# board_3.net
KiCad netlist of a schematic drawn in EAGLE
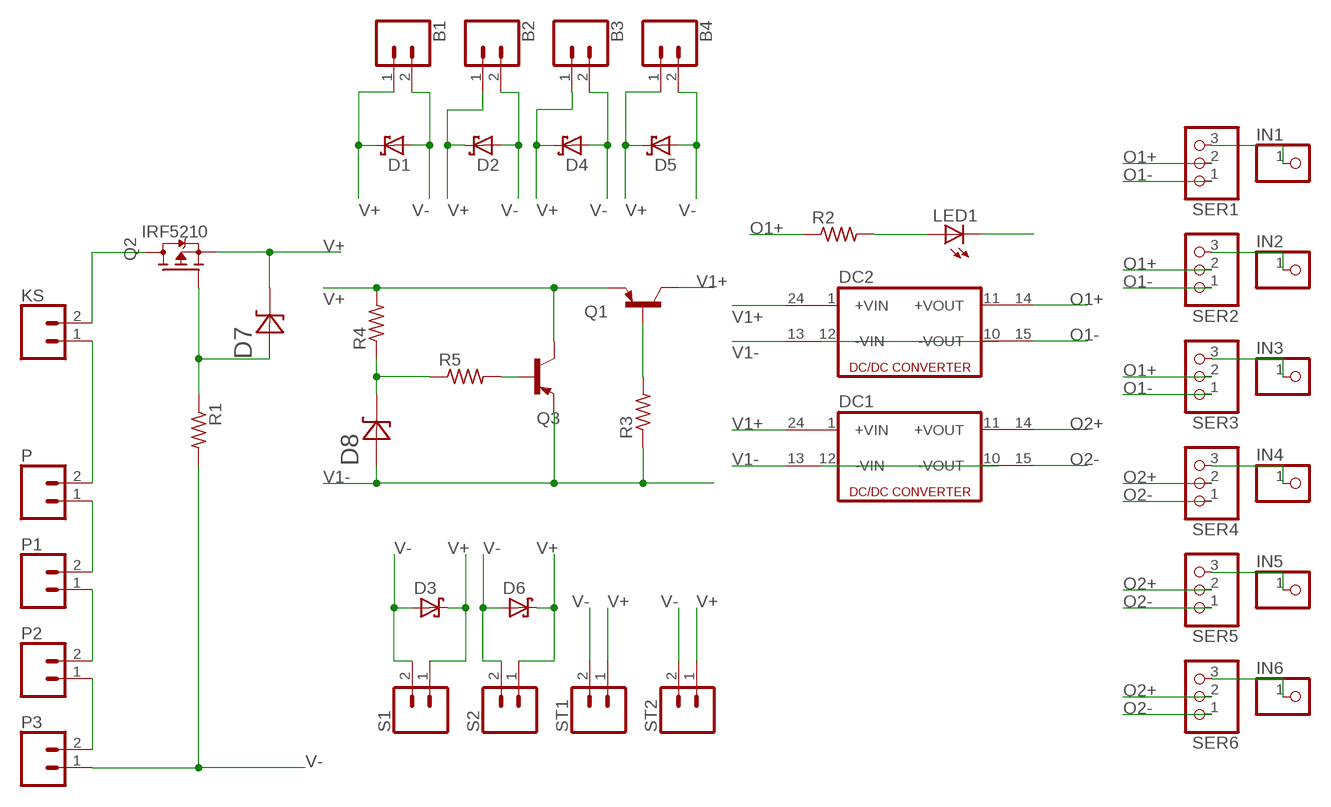
[diagram p0: schematic, sheet 1]

(export (version "E")
  (design (tool "Eeschema 10.0.6"))
  (components
    (comp (ref "B1")
      (value "CONN_02")
      (footprint "eagle-import:1X02")
      (libsource (lib "eagle-import") (part "CONN_02"))
    )
    (comp (ref "B2")
      (value "CONN_02")
      (footprint "eagle-import:1X02")
      (libsource (lib "eagle-import") (part "CONN_02"))
    )
    (comp (ref "B3")
      (value "CONN_02")
      (footprint "eagle-import:1X02")
      (libsource (lib "eagle-import") (part "CONN_02"))
    )
    (comp (ref "B4")
      (value "CONN_02")
      (footprint "eagle-import:1X02")
      (libsource (lib "eagle-import") (part "CONN_02"))
    )
    (comp (ref "D1")
      (value "SCHOTTKY-DIODEF126Z12")
      (footprint "eagle-import:F126Z12")
      (libsource (lib "eagle-import") (part "SCHOTTKY-DIODEF126Z12"))
    )
    (comp (ref "D2")
      (value "SCHOTTKY-DIODEF126Z12")
      (footprint "eagle-import:F126Z12")
      (libsource (lib "eagle-import") (part "SCHOTTKY-DIODEF126Z12"))
    )
    (comp (ref "D3")
      (value "SCHOTTKY-DIODEF126Z12")
      (footprint "eagle-import:F126Z12")
      (libsource (lib "eagle-import") (part "SCHOTTKY-DIODEF126Z12"))
    )
    (comp (ref "D4")
      (value "SCHOTTKY-DIODEF126Z12")
      (footprint "eagle-import:F126Z12")
      (libsource (lib "eagle-import") (part "SCHOTTKY-DIODEF126Z12"))
    )
    (comp (ref "D5")
      (value "SCHOTTKY-DIODEF126Z12")
      (footprint "eagle-import:F126Z12")
      (libsource (lib "eagle-import") (part "SCHOTTKY-DIODEF126Z12"))
    )
    (comp (ref "D6")
      (value "SCHOTTKY-DIODEF126Z12")
      (footprint "eagle-import:F126Z12")
      (libsource (lib "eagle-import") (part "SCHOTTKY-DIODEF126Z12"))
    )
    (comp (ref "D7")
      (value "1N4752A-T")
      (footprint "eagle-import:DIOAD1060W80L410D260")
      (fields (field (name "MF") "ON Semiconductor") (field (name "MP") "1N4752A"))
      (libsource (lib "eagle-import") (part "1N4752A-T"))
    )
    (comp (ref "D8")
      (value "1N4752A-T")
      (footprint "eagle-import:DIOAD1060W80L410D260")
      (fields (field (name "MF") "ON Semiconductor") (field (name "MP") "1N4752A"))
      (libsource (lib "eagle-import") (part "1N4752A-T"))
    )
    (comp (ref "DC1")
      (value "DC213R")
      (footprint "eagle-import:CMK")
      (libsource (lib "eagle-import") (part "DC213R"))
    )
    (comp (ref "DC2")
      (value "DC213R")
      (footprint "eagle-import:CMK")
      (libsource (lib "eagle-import") (part "DC213R"))
    )
    (comp (ref "IN1")
      (value "PINHD-1X1")
      (footprint "eagle-import:1X01")
      (libsource (lib "eagle-import") (part "PINHD-1X1"))
    )
    (comp (ref "IN2")
      (value "PINHD-1X1")
      (footprint "eagle-import:1X01")
      (libsource (lib "eagle-import") (part "PINHD-1X1"))
    )
    (comp (ref "IN3")
      (value "PINHD-1X1")
      (footprint "eagle-import:1X01")
      (libsource (lib "eagle-import") (part "PINHD-1X1"))
    )
    (comp (ref "IN4")
      (value "PINHD-1X1")
      (footprint "eagle-import:1X01")
      (libsource (lib "eagle-import") (part "PINHD-1X1"))
    )
    (comp (ref "IN5")
      (value "PINHD-1X1")
      (footprint "eagle-import:1X01")
      (libsource (lib "eagle-import") (part "PINHD-1X1"))
    )
    (comp (ref "IN6")
      (value "PINHD-1X1")
      (footprint "eagle-import:1X01")
      (libsource (lib "eagle-import") (part "PINHD-1X1"))
    )
    (comp (ref "KS")
      (value "CONN_02")
      (footprint "eagle-import:1X02")
      (libsource (lib "eagle-import") (part "CONN_02"))
    )
    (comp (ref "LED1")
      (value "LED5MM")
      (footprint "eagle-import:LED5MM")
      (libsource (lib "eagle-import") (part "LED5MM"))
    )
    (comp (ref "P")
      (value "CONN_02")
      (footprint "eagle-import:1X02")
      (libsource (lib "eagle-import") (part "CONN_02"))
    )
    (comp (ref "P1")
      (value "CONN_02")
      (footprint "eagle-import:1X02")
      (libsource (lib "eagle-import") (part "CONN_02"))
    )
    (comp (ref "P2")
      (value "CONN_02")
      (footprint "eagle-import:1X02")
      (libsource (lib "eagle-import") (part "CONN_02"))
    )
    (comp (ref "P3")
      (value "CONN_02")
      (footprint "eagle-import:1X02")
      (libsource (lib "eagle-import") (part "CONN_02"))
    )
    (comp (ref "Q1")
      (value "2N2907")
      (footprint "eagle-import:TO92-EBC-OVAL")
      (libsource (lib "eagle-import") (part "2N2907"))
    )
    (comp (ref "Q2")
      (value "IRF5210")
      (footprint "eagle-import:TO254P1054X469X2933-3")
      (fields (field (name "MF") "Infineon Technologies"))
      (libsource (lib "eagle-import") (part "IRF5210"))
    )
    (comp (ref "Q3")
      (value "2N2907")
      (footprint "eagle-import:TO92-EBC-OVAL")
      (libsource (lib "eagle-import") (part "2N2907"))
    )
    (comp (ref "R1")
      (value "R-US_0204/7")
      (footprint "eagle-import:0204_7")
      (libsource (lib "eagle-import") (part "R-US_0204/7"))
    )
    (comp (ref "R2")
      (value "R-US_0204/7")
      (footprint "eagle-import:0204_7")
      (libsource (lib "eagle-import") (part "R-US_0204/7"))
    )
    (comp (ref "R3")
      (value "R-US_0204/7")
      (footprint "eagle-import:0204_7")
      (libsource (lib "eagle-import") (part "R-US_0204/7"))
    )
    (comp (ref "R4")
      (value "R-US_0204/7")
      (footprint "eagle-import:0204_7")
      (libsource (lib "eagle-import") (part "R-US_0204/7"))
    )
    (comp (ref "R5")
      (value "R-US_0204/7")
      (footprint "eagle-import:0204_7")
      (libsource (lib "eagle-import") (part "R-US_0204/7"))
    )
    (comp (ref "S1")
      (value "CONN_02")
      (footprint "eagle-import:1X02")
      (libsource (lib "eagle-import") (part "CONN_02"))
    )
    (comp (ref "S2")
      (value "CONN_02")
      (footprint "eagle-import:1X02")
      (libsource (lib "eagle-import") (part "CONN_02"))
    )
    (comp (ref "SER1")
      (value "PINHD-1X3")
      (footprint "eagle-import:1X03")
      (libsource (lib "eagle-import") (part "PINHD-1X3"))
    )
    (comp (ref "SER2")
      (value "PINHD-1X3")
      (footprint "eagle-import:1X03")
      (libsource (lib "eagle-import") (part "PINHD-1X3"))
    )
    (comp (ref "SER3")
      (value "PINHD-1X3")
      (footprint "eagle-import:1X03")
      (libsource (lib "eagle-import") (part "PINHD-1X3"))
    )
    (comp (ref "SER4")
      (value "PINHD-1X3")
      (footprint "eagle-import:1X03")
      (libsource (lib "eagle-import") (part "PINHD-1X3"))
    )
    (comp (ref "SER5")
      (value "PINHD-1X3")
      (footprint "eagle-import:1X03")
      (libsource (lib "eagle-import") (part "PINHD-1X3"))
    )
    (comp (ref "SER6")
      (value "PINHD-1X3")
      (footprint "eagle-import:1X03")
      (libsource (lib "eagle-import") (part "PINHD-1X3"))
    )
    (comp (ref "ST1")
      (value "CONN_02")
      (footprint "eagle-import:1X02")
      (libsource (lib "eagle-import") (part "CONN_02"))
    )
    (comp (ref "ST2")
      (value "CONN_02")
      (footprint "eagle-import:1X02")
      (libsource (lib "eagle-import") (part "CONN_02"))
    )
  )
  (nets
    (net (code "1") (name "/O1+") (class "Default")
      (node (ref "DC2") (pin "14") (pinfunction "+VOUT1_14") (pintype "passive"))
      (node (ref "R2") (pin "1") (pinfunction "1_1") (pintype "passive"))
      (node (ref "SER1") (pin "2") (pinfunction "2_2") (pintype "passive"))
      (node (ref "SER2") (pin "2") (pinfunction "2_2") (pintype "passive"))
      (node (ref "SER3") (pin "2") (pinfunction "2_2") (pintype "passive"))
    )
    (net (code "2") (name "/O1-") (class "Default")
      (node (ref "DC2") (pin "15") (pinfunction "-VOUT1_15") (pintype "passive"))
      (node (ref "SER1") (pin "1") (pinfunction "1_1") (pintype "passive"))
      (node (ref "SER2") (pin "1") (pinfunction "1_1") (pintype "passive"))
      (node (ref "SER3") (pin "1") (pinfunction "1_1") (pintype "passive"))
    )
    (net (code "3") (name "/O2+") (class "Default")
      (node (ref "DC1") (pin "14") (pinfunction "+VOUT1_14") (pintype "passive"))
      (node (ref "SER4") (pin "2") (pinfunction "2_2") (pintype "passive"))
      (node (ref "SER5") (pin "2") (pinfunction "2_2") (pintype "passive"))
      (node (ref "SER6") (pin "2") (pinfunction "2_2") (pintype "passive"))
    )
    (net (code "4") (name "/O2-") (class "Default")
      (node (ref "DC1") (pin "15") (pinfunction "-VOUT1_15") (pintype "passive"))
      (node (ref "SER4") (pin "1") (pinfunction "1_1") (pintype "passive"))
      (node (ref "SER5") (pin "1") (pinfunction "1_1") (pintype "passive"))
      (node (ref "SER6") (pin "1") (pinfunction "1_1") (pintype "passive"))
    )
    (net (code "5") (name "/V+") (class "Default")
      (node (ref "B1") (pin "1") (pinfunction "1_1") (pintype "passive"))
      (node (ref "B2") (pin "1") (pinfunction "1_1") (pintype "passive"))
      (node (ref "B3") (pin "1") (pinfunction "1_1") (pintype "passive"))
      (node (ref "B4") (pin "1") (pinfunction "1_1") (pintype "passive"))
      (node (ref "D1") (pin "C") (pinfunction "C_C") (pintype "passive"))
      (node (ref "D2") (pin "C") (pinfunction "C_C") (pintype "passive"))
      (node (ref "D3") (pin "C") (pinfunction "C_C") (pintype "passive"))
      (node (ref "D4") (pin "C") (pinfunction "C_C") (pintype "passive"))
      (node (ref "D5") (pin "C") (pinfunction "C_C") (pintype "passive"))
      (node (ref "D6") (pin "C") (pinfunction "C_C") (pintype "passive"))
      (node (ref "D7") (pin "C") (pinfunction "C_C") (pintype "passive"))
      (node (ref "Q1") (pin "E") (pinfunction "E_E") (pintype "passive"))
      (node (ref "Q2") (pin "3") (pinfunction "S_3") (pintype "passive"))
      (node (ref "Q3") (pin "C") (pinfunction "C_C") (pintype "passive"))
      (node (ref "R4") (pin "2") (pinfunction "2_2") (pintype "passive"))
      (node (ref "S1") (pin "1") (pinfunction "1_1") (pintype "passive"))
      (node (ref "S2") (pin "1") (pinfunction "1_1") (pintype "passive"))
      (node (ref "ST1") (pin "1") (pinfunction "1_1") (pintype "passive"))
      (node (ref "ST2") (pin "1") (pinfunction "1_1") (pintype "passive"))
    )
    (net (code "6") (name "/V-") (class "Default")
      (node (ref "B1") (pin "2") (pinfunction "2_2") (pintype "passive"))
      (node (ref "B2") (pin "2") (pinfunction "2_2") (pintype "passive"))
      (node (ref "B3") (pin "2") (pinfunction "2_2") (pintype "passive"))
      (node (ref "B4") (pin "2") (pinfunction "2_2") (pintype "passive"))
      (node (ref "D1") (pin "A") (pinfunction "A_A") (pintype "passive"))
      (node (ref "D2") (pin "A") (pinfunction "A_A") (pintype "passive"))
      (node (ref "D3") (pin "A") (pinfunction "A_A") (pintype "passive"))
      (node (ref "D4") (pin "A") (pinfunction "A_A") (pintype "passive"))
      (node (ref "D5") (pin "A") (pinfunction "A_A") (pintype "passive"))
      (node (ref "D6") (pin "A") (pinfunction "A_A") (pintype "passive"))
      (node (ref "P3") (pin "1") (pinfunction "1_1") (pintype "passive"))
      (node (ref "R1") (pin "2") (pinfunction "2_2") (pintype "passive"))
      (node (ref "S1") (pin "2") (pinfunction "2_2") (pintype "passive"))
      (node (ref "S2") (pin "2") (pinfunction "2_2") (pintype "passive"))
      (node (ref "ST1") (pin "2") (pinfunction "2_2") (pintype "passive"))
      (node (ref "ST2") (pin "2") (pinfunction "2_2") (pintype "passive"))
    )
    (net (code "7") (name "/V1+") (class "Default")
      (node (ref "DC1") (pin "24") (pinfunction "+VIN1_24") (pintype "passive"))
      (node (ref "DC2") (pin "24") (pinfunction "+VIN1_24") (pintype "passive"))
      (node (ref "Q1") (pin "C") (pinfunction "C_C") (pintype "passive"))
    )
    (net (code "8") (name "/V1-") (class "Default")
      (node (ref "D8") (pin "A") (pinfunction "A_A") (pintype "passive"))
      (node (ref "DC1") (pin "13") (pinfunction "-VIN1_13") (pintype "passive"))
      (node (ref "DC2") (pin "13") (pinfunction "-VIN1_13") (pintype "passive"))
      (node (ref "Q3") (pin "E") (pinfunction "E_E") (pintype "passive"))
      (node (ref "R3") (pin "1") (pinfunction "1_1") (pintype "passive"))
    )
    (net (code "9") (name "Net-(D8-PadC)") (class "Default")
      (node (ref "D8") (pin "C") (pinfunction "C_C") (pintype "passive"))
      (node (ref "R4") (pin "1") (pinfunction "1_1") (pintype "passive"))
      (node (ref "R5") (pin "1") (pinfunction "1_1") (pintype "passive"))
    )
    (net (code "10") (name "Net-(DC1--VIN)") (class "Default")
      (node (ref "DC1") (pin "10") (pinfunction "-VOUT_10") (pintype "passive"))
      (node (ref "DC1") (pin "12") (pinfunction "-VIN_12") (pintype "passive"))
    )
    (net (code "11") (name "Net-(DC2--VIN)") (class "Default")
      (node (ref "DC2") (pin "10") (pinfunction "-VOUT_10") (pintype "passive"))
      (node (ref "DC2") (pin "12") (pinfunction "-VIN_12") (pintype "passive"))
    )
    (net (code "12") (name "Net-(IN1-Pad1)") (class "Default")
      (node (ref "IN1") (pin "1") (pinfunction "1_1") (pintype "passive"))
      (node (ref "SER1") (pin "3") (pinfunction "3_3") (pintype "passive"))
    )
    (net (code "13") (name "Net-(IN2-Pad1)") (class "Default")
      (node (ref "IN2") (pin "1") (pinfunction "1_1") (pintype "passive"))
      (node (ref "SER2") (pin "3") (pinfunction "3_3") (pintype "passive"))
    )
    (net (code "14") (name "Net-(IN3-Pad1)") (class "Default")
      (node (ref "IN3") (pin "1") (pinfunction "1_1") (pintype "passive"))
      (node (ref "SER3") (pin "3") (pinfunction "3_3") (pintype "passive"))
    )
    (net (code "15") (name "Net-(IN4-Pad1)") (class "Default")
      (node (ref "IN4") (pin "1") (pinfunction "1_1") (pintype "passive"))
      (node (ref "SER4") (pin "3") (pinfunction "3_3") (pintype "passive"))
    )
    (net (code "16") (name "Net-(IN5-Pad1)") (class "Default")
      (node (ref "IN5") (pin "1") (pinfunction "1_1") (pintype "passive"))
      (node (ref "SER5") (pin "3") (pinfunction "3_3") (pintype "passive"))
    )
    (net (code "17") (name "Net-(IN6-Pad1)") (class "Default")
      (node (ref "IN6") (pin "1") (pinfunction "1_1") (pintype "passive"))
      (node (ref "SER6") (pin "3") (pinfunction "3_3") (pintype "passive"))
    )
    (net (code "18") (name "Net-(KS-Pad1)") (class "Default")
      (node (ref "KS") (pin "1") (pinfunction "1_1") (pintype "passive"))
      (node (ref "P") (pin "2") (pinfunction "2_2") (pintype "passive"))
    )
    (net (code "19") (name "Net-(LED1-PadA)") (class "Default")
      (node (ref "LED1") (pin "A") (pinfunction "A_A") (pintype "passive"))
      (node (ref "R2") (pin "2") (pinfunction "2_2") (pintype "passive"))
    )
    (net (code "20") (name "Net-(P-Pad1)") (class "Default")
      (node (ref "P") (pin "1") (pinfunction "1_1") (pintype "passive"))
      (node (ref "P1") (pin "2") (pinfunction "2_2") (pintype "passive"))
    )
    (net (code "21") (name "Net-(P1-Pad1)") (class "Default")
      (node (ref "P1") (pin "1") (pinfunction "1_1") (pintype "passive"))
      (node (ref "P2") (pin "2") (pinfunction "2_2") (pintype "passive"))
    )
    (net (code "22") (name "Net-(P2-Pad1)") (class "Default")
      (node (ref "P2") (pin "1") (pinfunction "1_1") (pintype "passive"))
      (node (ref "P3") (pin "2") (pinfunction "2_2") (pintype "passive"))
    )
    (net (code "23") (name "Net-(Q1-PadB)") (class "Default")
      (node (ref "Q1") (pin "B") (pinfunction "B_B") (pintype "passive"))
      (node (ref "R3") (pin "2") (pinfunction "2_2") (pintype "passive"))
    )
    (net (code "24") (name "Net-(Q2-D)") (class "Default")
      (node (ref "KS") (pin "2") (pinfunction "2_2") (pintype "passive"))
      (node (ref "Q2") (pin "2") (pinfunction "D_2") (pintype "passive"))
    )
    (net (code "25") (name "Net-(Q2-G)") (class "Default")
      (node (ref "D7") (pin "A") (pinfunction "A_A") (pintype "passive"))
      (node (ref "Q2") (pin "1") (pinfunction "G_1") (pintype "passive"))
      (node (ref "R1") (pin "1") (pinfunction "1_1") (pintype "passive"))
    )
    (net (code "26") (name "Net-(Q3-PadB)") (class "Default")
      (node (ref "Q3") (pin "B") (pinfunction "B_B") (pintype "passive"))
      (node (ref "R5") (pin "2") (pinfunction "2_2") (pintype "passive"))
    )
    (net (code "27") (name "unconnected-(DC1-+VIN-Pad1)") (class "Default")
      (node (ref "DC1") (pin "1") (pinfunction "+VIN_1") (pintype "passive"))
    )
    (net (code "28") (name "unconnected-(DC1-+VOUT-Pad11)") (class "Default")
      (node (ref "DC1") (pin "11") (pinfunction "+VOUT_11") (pintype "passive"))
    )
    (net (code "29") (name "unconnected-(DC2-+VIN-Pad1)") (class "Default")
      (node (ref "DC2") (pin "1") (pinfunction "+VIN_1") (pintype "passive"))
    )
    (net (code "30") (name "unconnected-(DC2-+VOUT-Pad11)") (class "Default")
      (node (ref "DC2") (pin "11") (pinfunction "+VOUT_11") (pintype "passive"))
    )
    (net (code "31") (name "unconnected-(LED1-C-PadK)") (class "Default")
      (node (ref "LED1") (pin "K") (pinfunction "C_K") (pintype "passive"))
    )
  )
)
